# IQOV-164_Evo_board.net
KiCad netlist of a schematic drawn in EAGLE
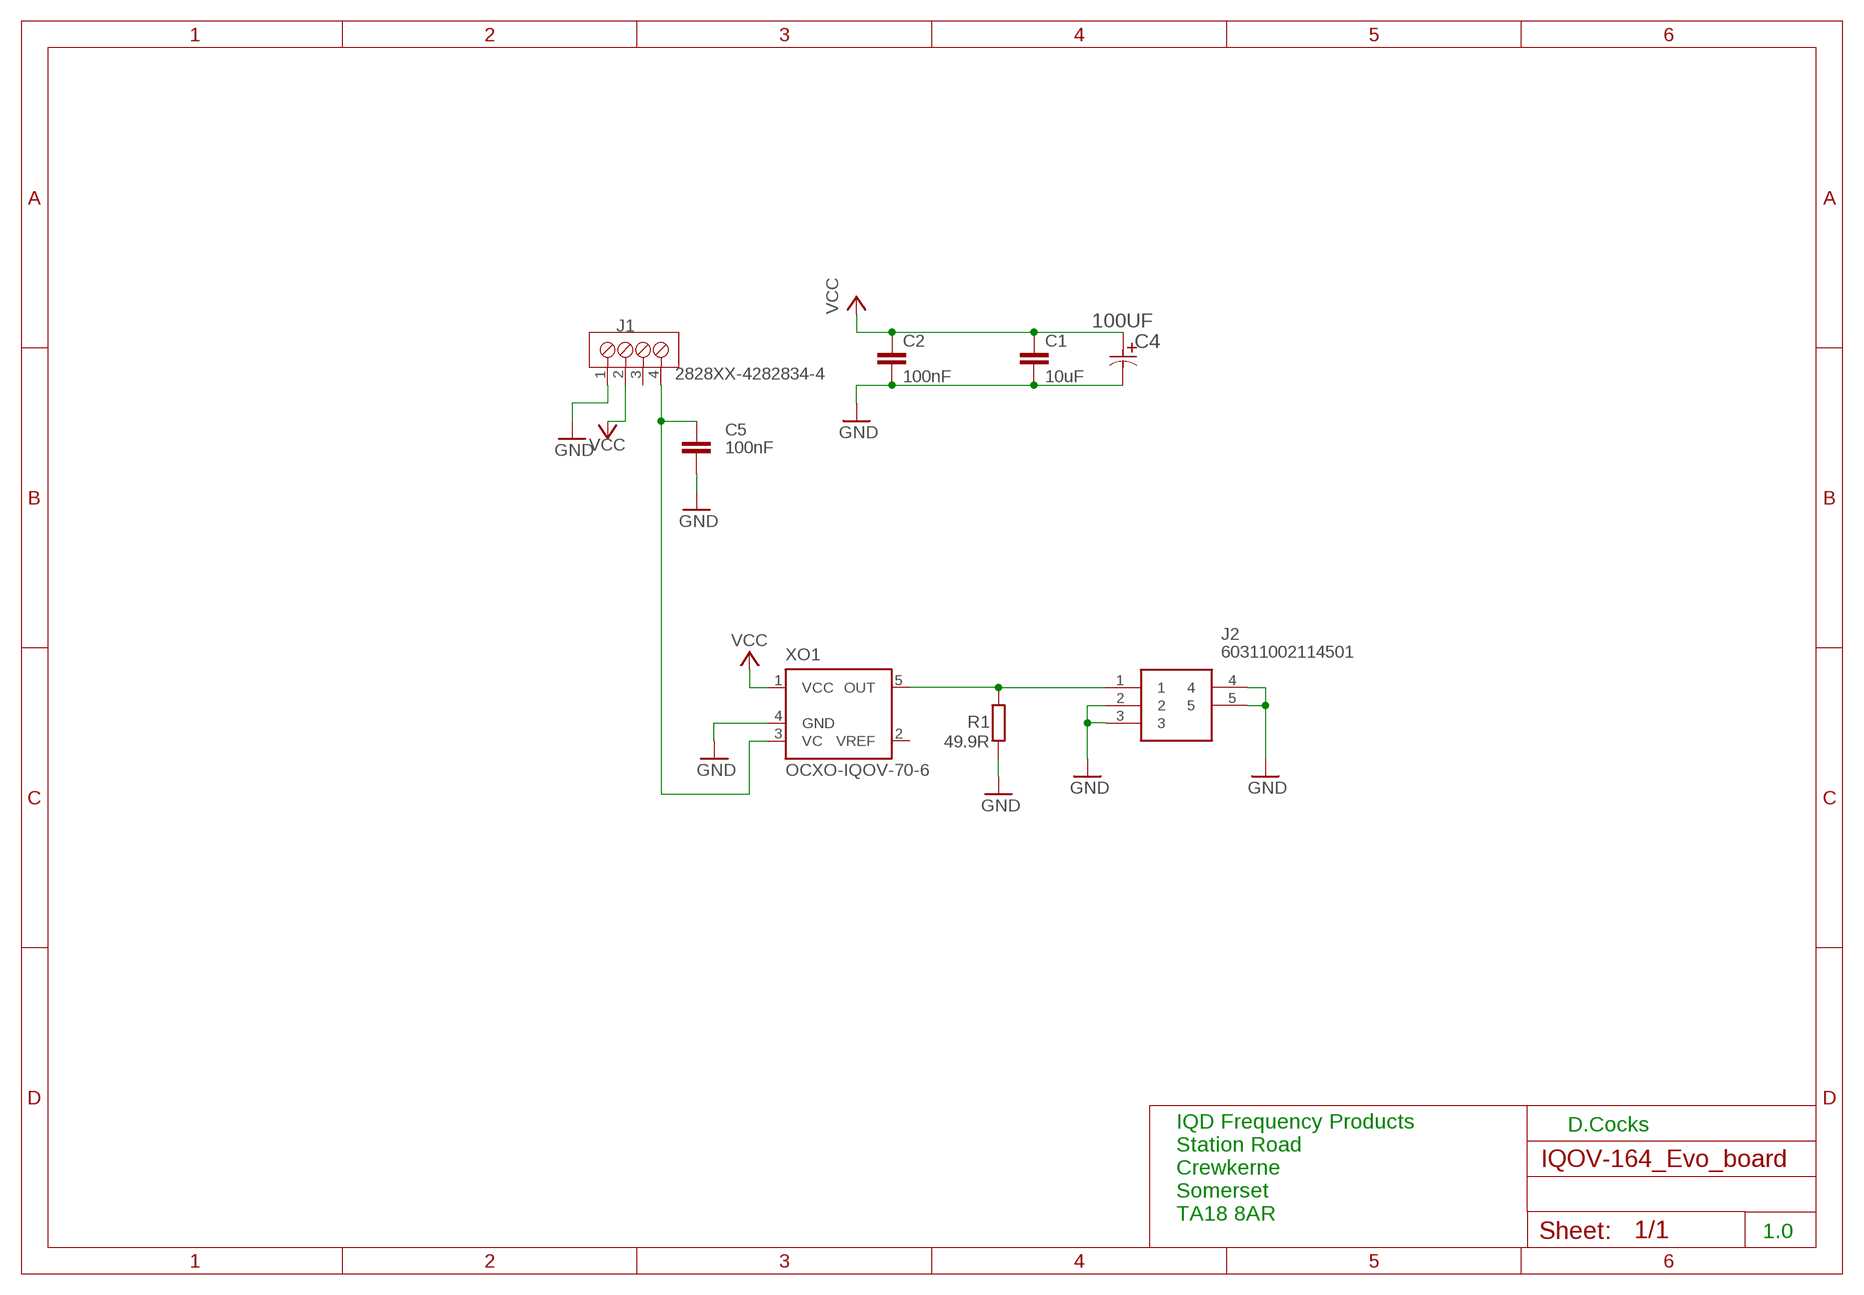
[diagram p0: schematic, sheet 1]

(export (version "E")
  (design (tool "Eeschema 10.0.6"))
  (components
    (comp (ref "C1")
      (value "10uF")
      (footprint "eagle-import:C0805")
      (libsource (lib "eagle-import") (part "C-EUC0805"))
    )
    (comp (ref "C2")
      (value "100nF")
      (footprint "eagle-import:C0805")
      (libsource (lib "eagle-import") (part "C-EUC0805"))
    )
    (comp (ref "C4")
      (value "100UF")
      (footprint "eagle-import:CAPAE530X610N")
      (fields (field (name "MPN") "EEE-FK0J101UR") (field (name "TOLERANCE") "±20 %"))
      (libsource (lib "eagle-import") (part "EEE--CASE-CFK0J101UR"))
    )
    (comp (ref "C5")
      (value "100nF")
      (footprint "eagle-import:C0805")
      (libsource (lib "eagle-import") (part "C-EUC0805"))
    )
    (comp (ref "J1")
      (value "2828XX-4282834-4")
      (footprint "eagle-import:TERMBLK_254-4N")
      (fields (field (name "MANUFACTURER") "TE Connectivity AMP Connectors") (field (name "MPN") "282834-4"))
      (libsource (lib "eagle-import") (part "2828XX-4282834-4"))
    )
    (comp (ref "J2")
      (value "60311002114501")
      (footprint "eagle-import:60312002114503")
      (fields
        (field (name "MANUFACTURER_PART_NUMBER") "60312002114503")
        (field (name "MOUSER_PART_NUMBER") "710-60312002114503")
      )
      (libsource (lib "eagle-import") (part "60312002114503"))
    )
    (comp (ref "R1")
      (value "49.9R")
      (footprint "eagle-import:M1206")
      (libsource (lib "eagle-import") (part "R-EU_M1206"))
    )
    (comp (ref "XO1")
      (value "OCXO-IQOV-70-6")
      (footprint "eagle-import:C0-08-8")
      (libsource (lib "eagle-import") (part "OCXO-IQOV-70-6"))
    )
  )
  (nets
    (net (code "1") (name "GND") (class "Default")
      (node (ref "C1") (pin "2") (pinfunction "2_2") (pintype "passive"))
      (node (ref "C2") (pin "2") (pinfunction "2_2") (pintype "passive"))
      (node (ref "C4") (pin "2") (pinfunction "2_2") (pintype "passive"))
      (node (ref "C5") (pin "2") (pinfunction "2_2") (pintype "passive"))
      (node (ref "J1") (pin "1") (pinfunction "1_1") (pintype "bidirectional"))
      (node (ref "J2") (pin "2") (pinfunction "2_2") (pintype "bidirectional"))
      (node (ref "J2") (pin "3") (pinfunction "3_3") (pintype "bidirectional"))
      (node (ref "J2") (pin "4") (pinfunction "4_4") (pintype "bidirectional"))
      (node (ref "J2") (pin "5") (pinfunction "5_5") (pintype "bidirectional"))
      (node (ref "R1") (pin "1") (pinfunction "1_1") (pintype "passive"))
      (node (ref "XO1") (pin "4") (pinfunction "GND_4") (pintype "power_in"))
    )
    (net (code "2") (name "Net-(XO1-OUT)") (class "Default")
      (node (ref "J2") (pin "1") (pinfunction "1_1") (pintype "bidirectional"))
      (node (ref "R1") (pin "2") (pinfunction "2_2") (pintype "passive"))
      (node (ref "XO1") (pin "5") (pinfunction "OUT_5") (pintype "output"))
    )
    (net (code "3") (name "Net-(XO1-VC)") (class "Default")
      (node (ref "C5") (pin "1") (pinfunction "1_1") (pintype "passive"))
      (node (ref "J1") (pin "4") (pinfunction "4_4") (pintype "bidirectional"))
      (node (ref "XO1") (pin "3") (pinfunction "VC_3") (pintype "input"))
    )
    (net (code "4") (name "VCC") (class "Default")
      (node (ref "C1") (pin "1") (pinfunction "1_1") (pintype "passive"))
      (node (ref "C2") (pin "1") (pinfunction "1_1") (pintype "passive"))
      (node (ref "C4") (pin "1") (pinfunction "1_1") (pintype "passive"))
      (node (ref "J1") (pin "2") (pinfunction "2_2") (pintype "bidirectional"))
      (node (ref "XO1") (pin "1") (pinfunction "VCC_1") (pintype "power_in"))
    )
    (net (code "5") (name "unconnected-(J1-Pad3)") (class "Default")
      (node (ref "J1") (pin "3") (pinfunction "3_3") (pintype "bidirectional"))
    )
    (net (code "6") (name "unconnected-(XO1-VREF-Pad2)") (class "Default")
      (node (ref "XO1") (pin "2") (pinfunction "VREF_2") (pintype "output"))
    )
  )
)
